# ground_station_boardv1_1.net
KiCad netlist of a schematic drawn in EAGLE
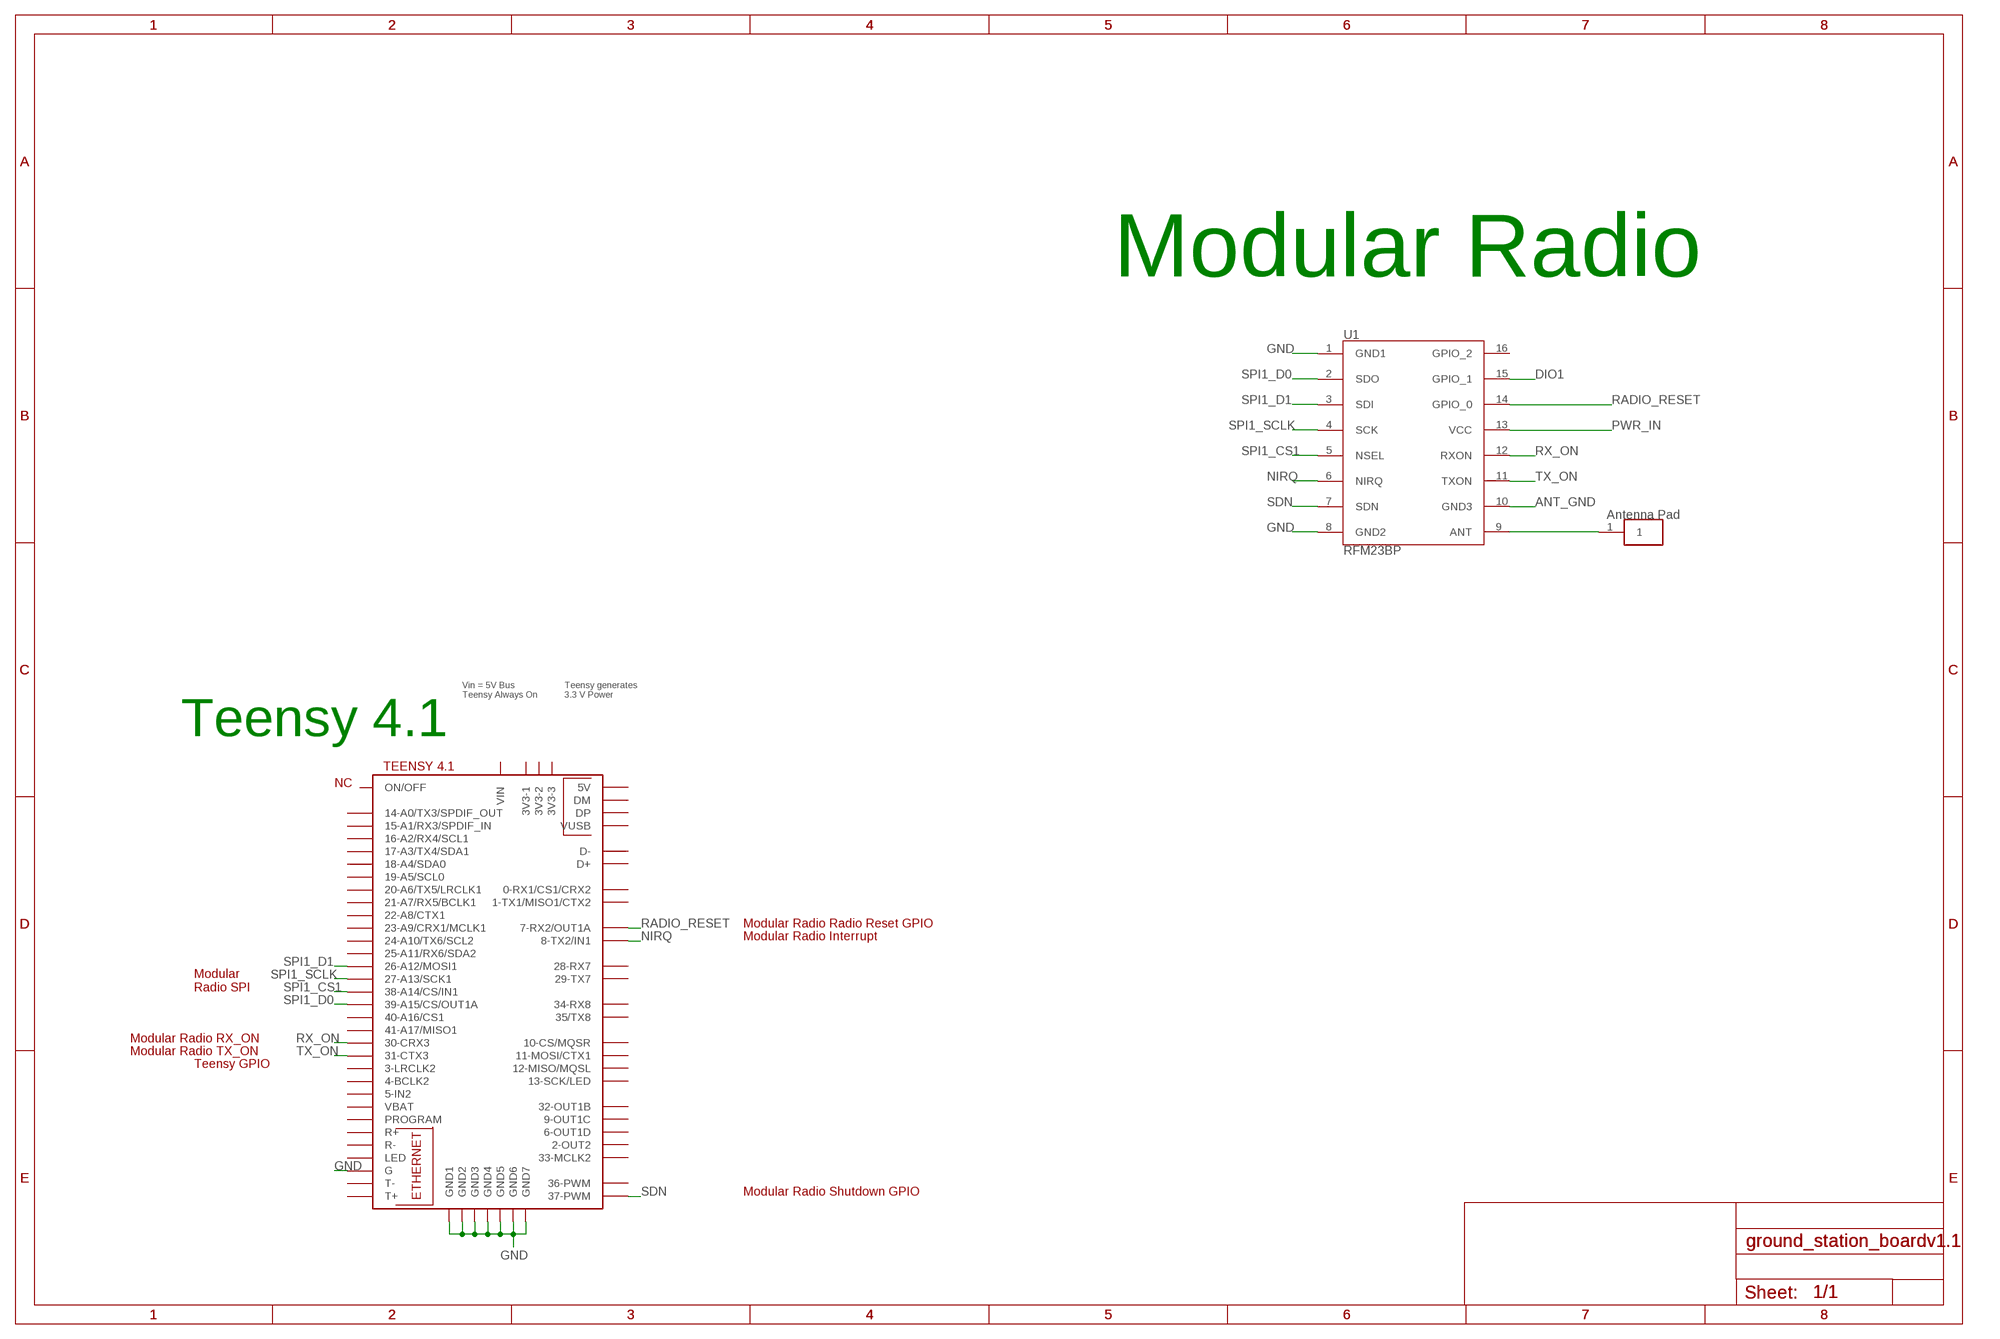
[diagram p0: schematic, sheet 1]

(export (version "E")
  (design (tool "Eeschema 10.0.6"))
  (components
    (comp (ref "U$1")
      (value "TEENSY41TEENSY")
      (footprint "eagle-import:TEENSY41")
      (libsource (lib "eagle-import") (part "TEENSY41TEENSY"))
    )
    (comp (ref "U$2")
      (value "ANTENNA_PAD+HOLES")
      (footprint "eagle-import:ANTENNA_PAD+HOLES")
      (libsource (lib "eagle-import") (part "ANTENNA_PAD+HOLES"))
    )
    (comp (ref "U1")
      (value "RFM23BP")
      (footprint "eagle-import:RFM23BP")
      (libsource (lib "eagle-import") (part "RFM23BP"))
    )
  )
  (nets
    (net (code "1") (name "/ANT_GND") (class "Default")
      (node (ref "U1") (pin "10") (pinfunction "GND3_10") (pintype "bidirectional"))
    )
    (net (code "2") (name "/DIO1") (class "Default")
      (node (ref "U1") (pin "15") (pinfunction "GPIO_1_15") (pintype "bidirectional"))
    )
    (net (code "3") (name "/GND") (class "Default")
      (node (ref "U$1") (pin "G") (pinfunction "G_G") (pintype "bidirectional"))
      (node (ref "U$1") (pin "GND") (pinfunction "GND7_GND") (pintype "bidirectional"))
      (node (ref "U$1") (pin "GND1") (pinfunction "GND1_GND1") (pintype "bidirectional"))
      (node (ref "U$1") (pin "GND2") (pinfunction "GND2_GND2") (pintype "bidirectional"))
      (node (ref "U$1") (pin "GND3") (pinfunction "GND3_GND3") (pintype "bidirectional"))
      (node (ref "U$1") (pin "GND4") (pinfunction "GND4_GND4") (pintype "bidirectional"))
      (node (ref "U$1") (pin "GND5") (pinfunction "GND5_GND5") (pintype "bidirectional"))
      (node (ref "U$1") (pin "GND6") (pinfunction "GND6_GND6") (pintype "bidirectional"))
      (node (ref "U1") (pin "1") (pinfunction "GND1_1") (pintype "bidirectional"))
      (node (ref "U1") (pin "8") (pinfunction "GND2_8") (pintype "bidirectional"))
    )
    (net (code "4") (name "/NIRQ") (class "Default")
      (node (ref "U$1") (pin "8-TX2/IN1") (pinfunction "8-TX2/IN1_8-TX2/IN1") (pintype "bidirectional"))
      (node (ref "U1") (pin "6") (pinfunction "NIRQ_6") (pintype "bidirectional"))
    )
    (net (code "5") (name "/PWR_IN") (class "Default")
      (node (ref "U1") (pin "13") (pinfunction "VCC_13") (pintype "bidirectional"))
    )
    (net (code "6") (name "/RADIO_RESET") (class "Default")
      (node (ref "U$1") (pin "7-RX2/OUT1A") (pinfunction "7-RX2/OUT1A_7-RX2/OUT1A") (pintype "bidirectional"))
      (node (ref "U1") (pin "14") (pinfunction "GPIO_0_14") (pintype "bidirectional"))
    )
    (net (code "7") (name "/RX_ON") (class "Default")
      (node (ref "U$1") (pin "30-CRX3") (pinfunction "30-CRX3_30-CRX3") (pintype "bidirectional"))
      (node (ref "U1") (pin "12") (pinfunction "RXON_12") (pintype "bidirectional"))
    )
    (net (code "8") (name "/SDN") (class "Default")
      (node (ref "U$1") (pin "37-PWM") (pinfunction "37-PWM_37-PWM") (pintype "bidirectional"))
      (node (ref "U1") (pin "7") (pinfunction "SDN_7") (pintype "bidirectional"))
    )
    (net (code "9") (name "/SPI1_CS1") (class "Default")
      (node (ref "U$1") (pin "38-A14/CS/IN1") (pinfunction "38-A14/CS/IN1_38-A14/CS/IN1") (pintype "bidirectional"))
      (node (ref "U1") (pin "5") (pinfunction "NSEL_5") (pintype "bidirectional"))
    )
    (net (code "10") (name "/SPI1_D0") (class "Default")
      (node (ref "U$1") (pin "39-A15/CS/OUT1A") (pinfunction "39-A15/CS/OUT1A_39-A15/CS/OUT1A") (pintype "bidirectional"))
      (node (ref "U1") (pin "2") (pinfunction "SDO_2") (pintype "bidirectional"))
    )
    (net (code "11") (name "/SPI1_D1") (class "Default")
      (node (ref "U$1") (pin "26-A12/MOSI1") (pinfunction "26-A12/MOSI1_26-A12/MOSI1") (pintype "bidirectional"))
      (node (ref "U1") (pin "3") (pinfunction "SDI_3") (pintype "bidirectional"))
    )
    (net (code "12") (name "/SPI1_SCLK") (class "Default")
      (node (ref "U$1") (pin "27-A13/SCK1") (pinfunction "27-A13/SCK1_27-A13/SCK1") (pintype "bidirectional"))
      (node (ref "U1") (pin "4") (pinfunction "SCK_4") (pintype "bidirectional"))
    )
    (net (code "13") (name "/TX_ON") (class "Default")
      (node (ref "U$1") (pin "31-CTX3") (pinfunction "31-CTX3_31-CTX3") (pintype "bidirectional"))
      (node (ref "U1") (pin "11") (pinfunction "TXON_11") (pintype "bidirectional"))
    )
    (net (code "14") (name "Net-(U1-ANT)") (class "Default")
      (node (ref "U$2") (pin "1") (pinfunction "1_1") (pintype "bidirectional"))
      (node (ref "U1") (pin "9") (pinfunction "ANT_9") (pintype "bidirectional"))
    )
    (net (code "15") (name "unconnected-(U$1-5V-Pad+5V)") (class "Default")
      (node (ref "U$1") (pin "+5V") (pinfunction "5V_+5V") (pintype "bidirectional"))
    )
    (net (code "16") (name "unconnected-(U$1-10-CS{slash}MQSR-Pad10-CS\\MQSR)") (class "Default")
      (node (ref "U$1") (pin "10-CS\\MQSR") (pinfunction "10-CS/MQSR_10-CS\\MQSR") (pintype "bidirectional"))
    )
    (net (code "17") (name "unconnected-(U$1-35{slash}TX8-Pad35-TX8)") (class "Default")
      (node (ref "U$1") (pin "35-TX8") (pinfunction "35/TX8_35-TX8") (pintype "bidirectional"))
    )
    (net (code "18") (name "unconnected-(U$1-Pad0-RX1{slash}CS1{slash}CRX2)") (class "Default")
      (node (ref "U$1") (pin "0-RX1/CS1/CRX2") (pinfunction "0-RX1/CS1/CRX2_0-RX1/CS1/CRX2") (pintype "bidirectional"))
    )
    (net (code "19") (name "unconnected-(U$1-Pad1-TX1{slash}MISO1{slash}CTX2)") (class "Default")
      (node (ref "U$1") (pin "1-TX1/MISO1/CTX2") (pinfunction "1-TX1/MISO1/CTX2_1-TX1/MISO1/CTX2") (pintype "bidirectional"))
    )
    (net (code "20") (name "unconnected-(U$1-Pad2-OUT2)") (class "Default")
      (node (ref "U$1") (pin "2-OUT2") (pinfunction "2-OUT2_2-OUT2") (pintype "bidirectional"))
    )
    (net (code "21") (name "unconnected-(U$1-Pad3-LRCLK2)") (class "Default")
      (node (ref "U$1") (pin "3-LRCLK2") (pinfunction "3-LRCLK2_3-LRCLK2") (pintype "bidirectional"))
    )
    (net (code "22") (name "unconnected-(U$1-Pad3V3-1)") (class "Default")
      (node (ref "U$1") (pin "3V3-1") (pinfunction "3V3-1_3V3-1") (pintype "bidirectional"))
    )
    (net (code "23") (name "unconnected-(U$1-Pad3V3-2)") (class "Default")
      (node (ref "U$1") (pin "3V3-2") (pinfunction "3V3-2_3V3-2") (pintype "bidirectional"))
    )
    (net (code "24") (name "unconnected-(U$1-Pad3V3-3)") (class "Default")
      (node (ref "U$1") (pin "3V3-3") (pinfunction "3V3-3_3V3-3") (pintype "bidirectional"))
    )
    (net (code "25") (name "unconnected-(U$1-Pad4-BCLK2)") (class "Default")
      (node (ref "U$1") (pin "4-BCLK2") (pinfunction "4-BCLK2_4-BCLK2") (pintype "bidirectional"))
    )
    (net (code "26") (name "unconnected-(U$1-Pad5-IN2)") (class "Default")
      (node (ref "U$1") (pin "5-IN2") (pinfunction "5-IN2_5-IN2") (pintype "bidirectional"))
    )
    (net (code "27") (name "unconnected-(U$1-Pad6-OUT1D)") (class "Default")
      (node (ref "U$1") (pin "6-OUT1D") (pinfunction "6-OUT1D_6-OUT1D") (pintype "bidirectional"))
    )
    (net (code "28") (name "unconnected-(U$1-Pad9-OUT1C)") (class "Default")
      (node (ref "U$1") (pin "9-OUT1C") (pinfunction "9-OUT1C_9-OUT1C") (pintype "bidirectional"))
    )
    (net (code "29") (name "unconnected-(U$1-Pad11-MOSI{slash}CTX1)") (class "Default")
      (node (ref "U$1") (pin "11-MOSI/CTX1") (pinfunction "11-MOSI/CTX1_11-MOSI/CTX1") (pintype "bidirectional"))
    )
    (net (code "30") (name "unconnected-(U$1-Pad12-MISO{slash}MQSL)") (class "Default")
      (node (ref "U$1") (pin "12-MISO/MQSL") (pinfunction "12-MISO/MQSL_12-MISO/MQSL") (pintype "bidirectional"))
    )
    (net (code "31") (name "unconnected-(U$1-Pad13-SCK{slash}LED)") (class "Default")
      (node (ref "U$1") (pin "13-SCK/LED") (pinfunction "13-SCK/LED_13-SCK/LED") (pintype "bidirectional"))
    )
    (net (code "32") (name "unconnected-(U$1-Pad14-A0{slash}TX3{slash}SPDIF_OUT)") (class "Default")
      (node (ref "U$1") (pin "14-A0/TX3/SPDIF_OUT") (pinfunction "14-A0/TX3/SPDIF_OUT_14-A0/TX3/SPDIF_OUT") (pintype "bidirectional"))
    )
    (net (code "33") (name "unconnected-(U$1-Pad15-A1{slash}RX3{slash}SPDIF_IN)") (class "Default")
      (node (ref "U$1") (pin "15-A1/RX3/SPDIF_IN") (pinfunction "15-A1/RX3/SPDIF_IN_15-A1/RX3/SPDIF_IN") (pintype "bidirectional"))
    )
    (net (code "34") (name "unconnected-(U$1-Pad16-A2{slash}RX4{slash}SCL1)") (class "Default")
      (node (ref "U$1") (pin "16-A2/RX4/SCL1") (pinfunction "16-A2/RX4/SCL1_16-A2/RX4/SCL1") (pintype "bidirectional"))
    )
    (net (code "35") (name "unconnected-(U$1-Pad17-A3{slash}TX4{slash}SDA1)") (class "Default")
      (node (ref "U$1") (pin "17-A3/TX4/SDA1") (pinfunction "17-A3/TX4/SDA1_17-A3/TX4/SDA1") (pintype "bidirectional"))
    )
    (net (code "36") (name "unconnected-(U$1-Pad18-A4{slash}SDA0)") (class "Default")
      (node (ref "U$1") (pin "18-A4/SDA0") (pinfunction "18-A4/SDA0_18-A4/SDA0") (pintype "bidirectional"))
    )
    (net (code "37") (name "unconnected-(U$1-Pad19-A5{slash}SCL0)") (class "Default")
      (node (ref "U$1") (pin "19-A5/SCL0") (pinfunction "19-A5/SCL0_19-A5/SCL0") (pintype "bidirectional"))
    )
    (net (code "38") (name "unconnected-(U$1-Pad20-A6{slash}TX5{slash}LRCLK1)") (class "Default")
      (node (ref "U$1") (pin "20-A6/TX5/LRCLK1") (pinfunction "20-A6/TX5/LRCLK1_20-A6/TX5/LRCLK1") (pintype "bidirectional"))
    )
    (net (code "39") (name "unconnected-(U$1-Pad21-A7{slash}RX5{slash}BCLK1)") (class "Default")
      (node (ref "U$1") (pin "21-A7/RX5/BCLK1") (pinfunction "21-A7/RX5/BCLK1_21-A7/RX5/BCLK1") (pintype "bidirectional"))
    )
    (net (code "40") (name "unconnected-(U$1-Pad22-A8{slash}CTX1)") (class "Default")
      (node (ref "U$1") (pin "22-A8/CTX1") (pinfunction "22-A8/CTX1_22-A8/CTX1") (pintype "bidirectional"))
    )
    (net (code "41") (name "unconnected-(U$1-Pad23-A9{slash}CRX1{slash}MCLK1)") (class "Default")
      (node (ref "U$1") (pin "23-A9/CRX1/MCLK1") (pinfunction "23-A9/CRX1/MCLK1_23-A9/CRX1/MCLK1") (pintype "bidirectional"))
    )
    (net (code "42") (name "unconnected-(U$1-Pad24-A10{slash}TX6{slash}SCL2)") (class "Default")
      (node (ref "U$1") (pin "24-A10/TX6/SCL2") (pinfunction "24-A10/TX6/SCL2_24-A10/TX6/SCL2") (pintype "bidirectional"))
    )
    (net (code "43") (name "unconnected-(U$1-Pad25-A11{slash}RX6{slash}SDA2)") (class "Default")
      (node (ref "U$1") (pin "25-A11/RX6/SDA2") (pinfunction "25-A11/RX6/SDA2_25-A11/RX6/SDA2") (pintype "bidirectional"))
    )
    (net (code "44") (name "unconnected-(U$1-Pad28-RX7)") (class "Default")
      (node (ref "U$1") (pin "28-RX7") (pinfunction "28-RX7_28-RX7") (pintype "bidirectional"))
    )
    (net (code "45") (name "unconnected-(U$1-Pad29-TX7)") (class "Default")
      (node (ref "U$1") (pin "29-TX7") (pinfunction "29-TX7_29-TX7") (pintype "bidirectional"))
    )
    (net (code "46") (name "unconnected-(U$1-Pad32-OUT1B)") (class "Default")
      (node (ref "U$1") (pin "32-OUT1B") (pinfunction "32-OUT1B_32-OUT1B") (pintype "bidirectional"))
    )
    (net (code "47") (name "unconnected-(U$1-Pad33-MCLK2)") (class "Default")
      (node (ref "U$1") (pin "33-MCLK2") (pinfunction "33-MCLK2_33-MCLK2") (pintype "bidirectional"))
    )
    (net (code "48") (name "unconnected-(U$1-Pad34-RX8)") (class "Default")
      (node (ref "U$1") (pin "34-RX8") (pinfunction "34-RX8_34-RX8") (pintype "bidirectional"))
    )
    (net (code "49") (name "unconnected-(U$1-Pad36-PWM)") (class "Default")
      (node (ref "U$1") (pin "36-PWM") (pinfunction "36-PWM_36-PWM") (pintype "bidirectional"))
    )
    (net (code "50") (name "unconnected-(U$1-Pad40-A16{slash}CS1)") (class "Default")
      (node (ref "U$1") (pin "40-A16/CS1") (pinfunction "40-A16/CS1_40-A16/CS1") (pintype "bidirectional"))
    )
    (net (code "51") (name "unconnected-(U$1-Pad41-A17{slash}MISO1)") (class "Default")
      (node (ref "U$1") (pin "41-A17/MISO1") (pinfunction "41-A17/MISO1_41-A17/MISO1") (pintype "bidirectional"))
    )
    (net (code "52") (name "unconnected-(U$1-PadD+)") (class "Default")
      (node (ref "U$1") (pin "D+") (pinfunction "D+_D+") (pintype "bidirectional"))
    )
    (net (code "53") (name "unconnected-(U$1-PadD-)") (class "Default")
      (node (ref "U$1") (pin "D-") (pinfunction "D-_D-") (pintype "bidirectional"))
    )
    (net (code "54") (name "unconnected-(U$1-PadDM)") (class "Default")
      (node (ref "U$1") (pin "DM") (pinfunction "DM_DM") (pintype "bidirectional"))
    )
    (net (code "55") (name "unconnected-(U$1-PadDP)") (class "Default")
      (node (ref "U$1") (pin "DP") (pinfunction "DP_DP") (pintype "bidirectional"))
    )
    (net (code "56") (name "unconnected-(U$1-PadLED)") (class "Default")
      (node (ref "U$1") (pin "LED") (pinfunction "LED_LED") (pintype "bidirectional"))
    )
    (net (code "57") (name "unconnected-(U$1-PadON{slash}OFF)") (class "Default")
      (node (ref "U$1") (pin "ON/OFF") (pinfunction "ON/OFF_ON/OFF") (pintype "bidirectional"))
    )
    (net (code "58") (name "unconnected-(U$1-PadPROGRAM)") (class "Default")
      (node (ref "U$1") (pin "PROGRAM") (pinfunction "PROGRAM_PROGRAM") (pintype "bidirectional"))
    )
    (net (code "59") (name "unconnected-(U$1-PadR+)") (class "Default")
      (node (ref "U$1") (pin "R+") (pinfunction "R+_R+") (pintype "bidirectional"))
    )
    (net (code "60") (name "unconnected-(U$1-PadR-)") (class "Default")
      (node (ref "U$1") (pin "R-") (pinfunction "R-_R-") (pintype "bidirectional"))
    )
    (net (code "61") (name "unconnected-(U$1-PadT+)") (class "Default")
      (node (ref "U$1") (pin "T+") (pinfunction "T+_T+") (pintype "bidirectional"))
    )
    (net (code "62") (name "unconnected-(U$1-PadT-)") (class "Default")
      (node (ref "U$1") (pin "T-") (pinfunction "T-_T-") (pintype "bidirectional"))
    )
    (net (code "63") (name "unconnected-(U$1-PadVBAT)") (class "Default")
      (node (ref "U$1") (pin "VBAT") (pinfunction "VBAT_VBAT") (pintype "bidirectional"))
    )
    (net (code "64") (name "unconnected-(U$1-PadVIN)") (class "Default")
      (node (ref "U$1") (pin "VIN") (pinfunction "VIN_VIN") (pintype "bidirectional"))
    )
    (net (code "65") (name "unconnected-(U$1-PadVUSB)") (class "Default")
      (node (ref "U$1") (pin "VUSB") (pinfunction "VUSB_VUSB") (pintype "bidirectional"))
    )
    (net (code "66") (name "unconnected-(U1-GPIO_2-Pad16)") (class "Default")
      (node (ref "U1") (pin "16") (pinfunction "GPIO_2_16") (pintype "bidirectional"))
    )
  )
)
